# LoRa_Gateway_ESP32_-_DRAFT_3.net
KiCad netlist of a schematic drawn in EAGLE
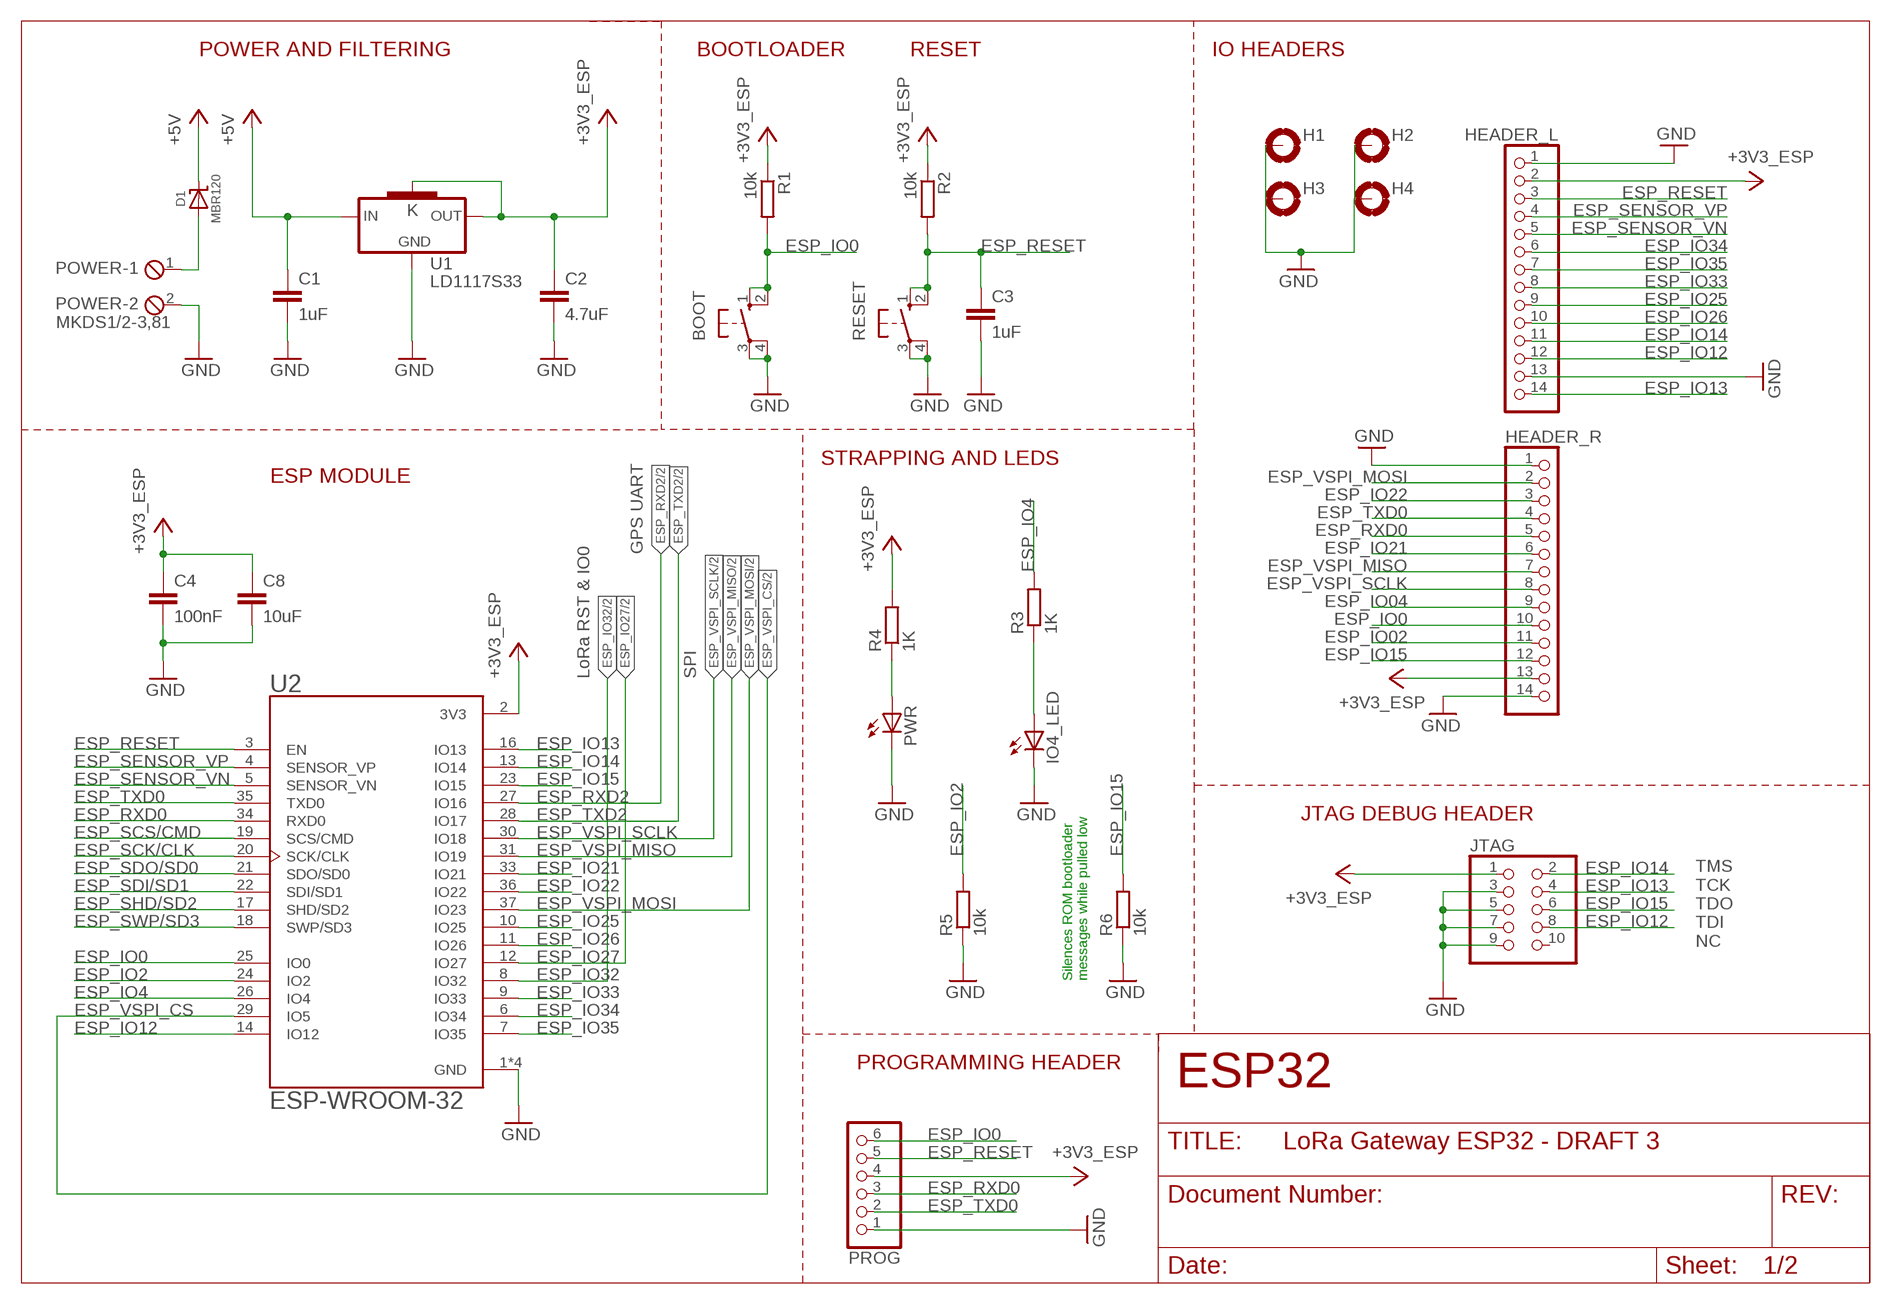
[diagram p0: schematic, sheet 1]
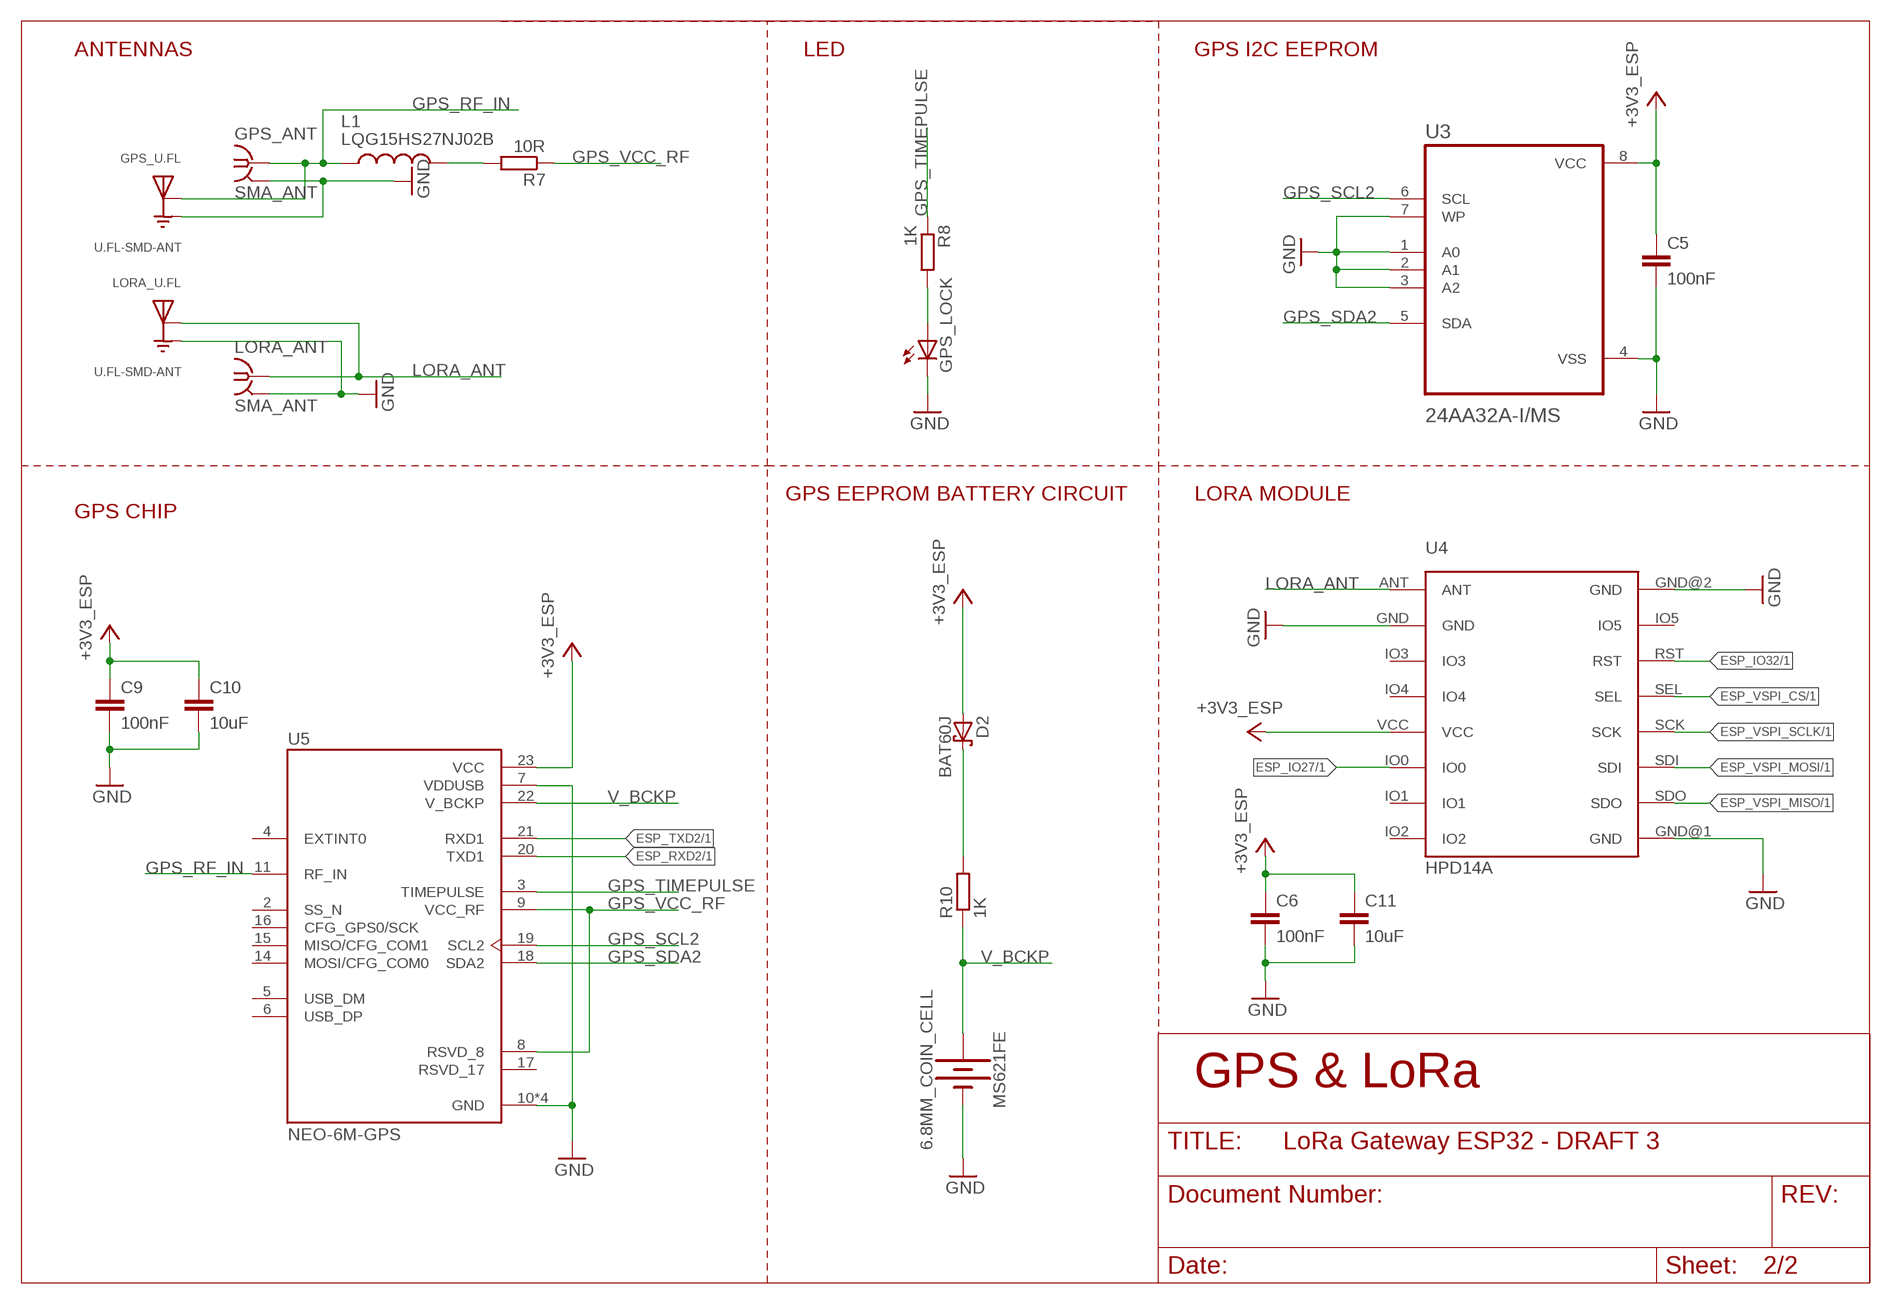
[diagram p1: schematic, sheet 2]

(export (version "E")
  (design (tool "Eeschema 10.0.6"))
  (components
    (comp (ref "C5")
      (value "100nF")
      (footprint "eagle-import:C0805K")
      (libsource (lib "eagle-import") (part "C-EUC0805K"))
    )
    (comp (ref "C6")
      (value "100nF")
      (footprint "eagle-import:C0805K")
      (libsource (lib "eagle-import") (part "C-EUC0805K"))
    )
    (comp (ref "C9")
      (value "100nF")
      (footprint "eagle-import:C0805K")
      (libsource (lib "eagle-import") (part "C-EUC0805K"))
    )
    (comp (ref "C10")
      (value "10uF")
      (footprint "eagle-import:C0805K")
      (libsource (lib "eagle-import") (part "C-EUC0805K"))
    )
    (comp (ref "C11")
      (value "10uF")
      (footprint "eagle-import:C0805K")
      (libsource (lib "eagle-import") (part "C-EUC0805K"))
    )
    (comp (ref "D2")
      (value "BAT60J")
      (footprint "eagle-import:SOD323_ST")
      (libsource (lib "eagle-import") (part "BAT60J"))
    )
    (comp (ref "GPS_ANT")
      (value "SMA_ANT")
      (footprint "eagle-import:BU-SMA-H")
      (libsource (lib "eagle-import") (part "SMA_ANT"))
    )
    (comp (ref "GPS_LOCK")
      (value "LEDCHIP-LED0805")
      (footprint "eagle-import:CHIP-LED0805")
      (libsource (lib "eagle-import") (part "LEDCHIP-LED0805"))
    )
    (comp (ref "GPS_U.FL")
      (value "U.FL-SMD-ANT")
      (footprint "eagle-import:HRS_U.FL-R-SMT-1(10)")
      (fields (field (name "MF") "Hirose") (field (name "MP") "U.FL-R-SMT-1(10)"))
      (libsource (lib "eagle-import") (part "U.FL-SMD-ANT"))
    )
    (comp (ref "L1")
      (value "LQG15HS27NJ02B")
      (footprint "eagle-import:INDC1005X55N")
      (fields (field (name "MF") "Murata"))
      (libsource (lib "eagle-import") (part "LQG15HS27NJ02B"))
    )
    (comp (ref "LORA_ANT")
      (value "SMA_ANT")
      (footprint "eagle-import:BU-SMA-H")
      (libsource (lib "eagle-import") (part "SMA_ANT"))
    )
    (comp (ref "LORA_U.FL")
      (value "U.FL-SMD-ANT")
      (footprint "eagle-import:HRS_U.FL-R-SMT-1(10)")
      (fields (field (name "MF") "Hirose") (field (name "MP") "U.FL-R-SMT-1(10)"))
      (libsource (lib "eagle-import") (part "U.FL-SMD-ANT"))
    )
    (comp (ref "MS621FE")
      (value "6.8MM_COIN_CELL")
      (footprint "eagle-import:BATTCON-6.8MM")
      (libsource (lib "eagle-import") (part "BATTERY-6.8MM_SMD"))
    )
    (comp (ref "R7")
      (value "10R")
      (footprint "eagle-import:R0805")
      (libsource (lib "eagle-import") (part "R-EU_R0805"))
    )
    (comp (ref "R8")
      (value "1K")
      (footprint "eagle-import:R0805")
      (libsource (lib "eagle-import") (part "R-EU_R0805"))
    )
    (comp (ref "R10")
      (value "1K")
      (footprint "eagle-import:R0805")
      (libsource (lib "eagle-import") (part "R-EU_R0805"))
    )
    (comp (ref "U3")
      (value "24AA32A-I/MS")
      (footprint "eagle-import:SOP65P490X110-8N")
      (fields (field (name "MF") "Microchip"))
      (libsource (lib "eagle-import") (part "24AA32A-I/MS"))
    )
    (comp (ref "U4")
      (value "HPD14A")
      (footprint "eagle-import:HPD14A")
      (libsource (lib "eagle-import") (part "HPD14A"))
    )
    (comp (ref "U5")
      (value "NEO-6M-GPS")
      (footprint "eagle-import:XCVR_NEO-6M-GPS")
      (fields (field (name "MF") "u-blox"))
      (libsource (lib "eagle-import") (part "NEO-6M-GPS"))
    )
    (comp (ref "BOOT")
      (value "10-XX")
      (footprint "eagle-import:B3F-10XX")
      (fields (field (name "MPN") "B3F-1000"))
      (libsource (lib "eagle-import") (part "10-XX"))
    )
    (comp (ref "C1")
      (value "1uF")
      (footprint "eagle-import:C0805K")
      (libsource (lib "eagle-import") (part "C-EUC0805K"))
    )
    (comp (ref "C2")
      (value "4.7uF")
      (footprint "eagle-import:C0805K")
      (libsource (lib "eagle-import") (part "C-EUC0805K"))
    )
    (comp (ref "C3")
      (value "1uF")
      (footprint "eagle-import:C0805K")
      (libsource (lib "eagle-import") (part "C-EUC0805K"))
    )
    (comp (ref "C4")
      (value "100nF")
      (footprint "eagle-import:C0805K")
      (libsource (lib "eagle-import") (part "C-EUC0805K"))
    )
    (comp (ref "C8")
      (value "10uF")
      (footprint "eagle-import:C0805K")
      (libsource (lib "eagle-import") (part "C-EUC0805K"))
    )
    (comp (ref "D1")
      (value "MBR120")
      (footprint "eagle-import:SOD-123")
      (libsource (lib "eagle-import") (part "DIODE-SCHOTTKYSOD-123"))
    )
    (comp (ref "H1")
      (value "MOUNT-PAD-ROUND3.2")
      (footprint "eagle-import:3,2-PAD")
      (libsource (lib "eagle-import") (part "MOUNT-PAD-ROUND3.2"))
    )
    (comp (ref "H2")
      (value "MOUNT-PAD-ROUND3.2")
      (footprint "eagle-import:3,2-PAD")
      (libsource (lib "eagle-import") (part "MOUNT-PAD-ROUND3.2"))
    )
    (comp (ref "H3")
      (value "MOUNT-PAD-ROUND3.2")
      (footprint "eagle-import:3,2-PAD")
      (libsource (lib "eagle-import") (part "MOUNT-PAD-ROUND3.2"))
    )
    (comp (ref "H4")
      (value "MOUNT-PAD-ROUND3.2")
      (footprint "eagle-import:3,2-PAD")
      (libsource (lib "eagle-import") (part "MOUNT-PAD-ROUND3.2"))
    )
    (comp (ref "HEADER_L")
      (value "PINHD-1X14")
      (footprint "eagle-import:1X14")
      (libsource (lib "eagle-import") (part "PINHD-1X14"))
    )
    (comp (ref "HEADER_R")
      (value "PINHD-1X14")
      (footprint "eagle-import:1X14")
      (libsource (lib "eagle-import") (part "PINHD-1X14"))
    )
    (comp (ref "IO4_LED")
      (value "LEDCHIP-LED0805")
      (footprint "eagle-import:CHIP-LED0805")
      (libsource (lib "eagle-import") (part "LEDCHIP-LED0805"))
    )
    (comp (ref "JTAG")
      (value "PINHD-2X5")
      (footprint "eagle-import:2X05")
      (libsource (lib "eagle-import") (part "PINHD-2X5"))
    )
    (comp (ref "POWER")
      (value "MKDS1/2-3,81")
      (footprint "eagle-import:2POL381")
      (libsource (lib "eagle-import") (part "MKDS1/2-3,81"))
    )
    (comp (ref "PROG")
      (value "PINHD-1X6")
      (footprint "eagle-import:1X06")
      (libsource (lib "eagle-import") (part "PINHD-1X6"))
    )
    (comp (ref "PWR")
      (value "LEDCHIP-LED0805")
      (footprint "eagle-import:CHIP-LED0805")
      (libsource (lib "eagle-import") (part "LEDCHIP-LED0805"))
    )
    (comp (ref "R1")
      (value "10k")
      (footprint "eagle-import:R0805")
      (libsource (lib "eagle-import") (part "R-EU_R0805"))
    )
    (comp (ref "R2")
      (value "10k")
      (footprint "eagle-import:R0805")
      (libsource (lib "eagle-import") (part "R-EU_R0805"))
    )
    (comp (ref "R3")
      (value "1K")
      (footprint "eagle-import:R0805")
      (libsource (lib "eagle-import") (part "R-EU_R0805"))
    )
    (comp (ref "R4")
      (value "1K")
      (footprint "eagle-import:R0805")
      (libsource (lib "eagle-import") (part "R-EU_R0805"))
    )
    (comp (ref "R5")
      (value "10k")
      (footprint "eagle-import:R0805")
      (libsource (lib "eagle-import") (part "R-EU_R0805"))
    )
    (comp (ref "R6")
      (value "10k")
      (footprint "eagle-import:R0805")
      (libsource (lib "eagle-import") (part "R-EU_R0805"))
    )
    (comp (ref "RESET")
      (value "10-XX")
      (footprint "eagle-import:B3F-10XX")
      (fields (field (name "MPN") "B3F-1000"))
      (libsource (lib "eagle-import") (part "10-XX"))
    )
    (comp (ref "U1")
      (value "LD1117S33")
      (footprint "eagle-import:SOT223")
      (fields (field (name "MF") "STMicroelectronics"))
      (libsource (lib "eagle-import") (part "LD1117S33"))
    )
    (comp (ref "U2")
      (value "ESP-WROOM-32")
      (footprint "eagle-import:MODULE_ESP-WROOM-32")
      (fields (field (name "MF") "Olimex LTD"))
      (libsource (lib "eagle-import") (part "ESP-WROOM-32"))
    )
  )
  (nets
    (net (code "1") (name "+3V3_ESP") (class "Default")
      (node (ref "C10") (pin "1") (pinfunction "1_1") (pintype "passive"))
      (node (ref "C11") (pin "1") (pinfunction "1_1") (pintype "passive"))
      (node (ref "C2") (pin "1") (pinfunction "1_1") (pintype "passive"))
      (node (ref "C4") (pin "1") (pinfunction "1_1") (pintype "passive"))
      (node (ref "C5") (pin "1") (pinfunction "1_1") (pintype "passive"))
      (node (ref "C6") (pin "1") (pinfunction "1_1") (pintype "passive"))
      (node (ref "C8") (pin "1") (pinfunction "1_1") (pintype "passive"))
      (node (ref "C9") (pin "1") (pinfunction "1_1") (pintype "passive"))
      (node (ref "D2") (pin "A") (pinfunction "A_A") (pintype "passive"))
      (node (ref "HEADER_L") (pin "2") (pinfunction "2_2") (pintype "passive"))
      (node (ref "HEADER_R") (pin "13") (pinfunction "13_13") (pintype "passive"))
      (node (ref "JTAG") (pin "1") (pinfunction "1_1") (pintype "passive"))
      (node (ref "PROG") (pin "4") (pinfunction "4_4") (pintype "passive"))
      (node (ref "R1") (pin "1") (pinfunction "1_1") (pintype "passive"))
      (node (ref "R2") (pin "1") (pinfunction "1_1") (pintype "passive"))
      (node (ref "R4") (pin "2") (pinfunction "2_2") (pintype "passive"))
      (node (ref "U1") (pin "2") (pinfunction "OUT_2") (pintype "passive"))
      (node (ref "U1") (pin "4") (pinfunction "K_4") (pintype "passive"))
      (node (ref "U2") (pin "2") (pinfunction "3V3_2") (pintype "power_in"))
      (node (ref "U3") (pin "8") (pinfunction "VCC_8") (pintype "power_in"))
      (node (ref "U4") (pin "VCC") (pinfunction "VCC_VCC") (pintype "bidirectional"))
      (node (ref "U5") (pin "23") (pinfunction "VCC_23") (pintype "power_in"))
    )
    (net (code "2") (name "+5V") (class "Default")
      (node (ref "C1") (pin "1") (pinfunction "1_1") (pintype "passive"))
      (node (ref "D1") (pin "C") (pinfunction "C_C") (pintype "passive"))
      (node (ref "U1") (pin "3") (pinfunction "IN_3") (pintype "input"))
    )
    (net (code "3") (name "ESP_IO0") (class "Default")
      (node (ref "BOOT") (pin "1") (pinfunction "S_1") (pintype "passive"))
      (node (ref "BOOT") (pin "2") (pinfunction "S1_2") (pintype "passive"))
      (node (ref "HEADER_R") (pin "10") (pinfunction "10_10") (pintype "passive"))
      (node (ref "PROG") (pin "6") (pinfunction "6_6") (pintype "passive"))
      (node (ref "R1") (pin "2") (pinfunction "2_2") (pintype "passive"))
      (node (ref "U2") (pin "25") (pinfunction "IO0_25") (pintype "bidirectional"))
    )
    (net (code "4") (name "ESP_IO2") (class "Default")
      (node (ref "R5") (pin "2") (pinfunction "2_2") (pintype "passive"))
      (node (ref "U2") (pin "24") (pinfunction "IO2_24") (pintype "bidirectional"))
    )
    (net (code "5") (name "ESP_IO02") (class "Default")
      (node (ref "HEADER_R") (pin "11") (pinfunction "11_11") (pintype "passive"))
    )
    (net (code "6") (name "ESP_IO4") (class "Default")
      (node (ref "R3") (pin "2") (pinfunction "2_2") (pintype "passive"))
      (node (ref "U2") (pin "26") (pinfunction "IO4_26") (pintype "bidirectional"))
    )
    (net (code "7") (name "ESP_IO04") (class "Default")
      (node (ref "HEADER_R") (pin "9") (pinfunction "9_9") (pintype "passive"))
    )
    (net (code "8") (name "ESP_IO12") (class "Default")
      (node (ref "HEADER_L") (pin "12") (pinfunction "12_12") (pintype "passive"))
      (node (ref "JTAG") (pin "8") (pinfunction "8_8") (pintype "passive"))
      (node (ref "U2") (pin "14") (pinfunction "IO12_14") (pintype "bidirectional"))
    )
    (net (code "9") (name "ESP_IO13") (class "Default")
      (node (ref "HEADER_L") (pin "14") (pinfunction "14_14") (pintype "passive"))
      (node (ref "JTAG") (pin "4") (pinfunction "4_4") (pintype "passive"))
      (node (ref "U2") (pin "16") (pinfunction "IO13_16") (pintype "bidirectional"))
    )
    (net (code "10") (name "ESP_IO14") (class "Default")
      (node (ref "HEADER_L") (pin "11") (pinfunction "11_11") (pintype "passive"))
      (node (ref "JTAG") (pin "2") (pinfunction "2_2") (pintype "passive"))
      (node (ref "U2") (pin "13") (pinfunction "IO14_13") (pintype "bidirectional"))
    )
    (net (code "11") (name "ESP_IO15") (class "Default")
      (node (ref "HEADER_R") (pin "12") (pinfunction "12_12") (pintype "passive"))
      (node (ref "JTAG") (pin "6") (pinfunction "6_6") (pintype "passive"))
      (node (ref "R6") (pin "2") (pinfunction "2_2") (pintype "passive"))
      (node (ref "U2") (pin "23") (pinfunction "IO15_23") (pintype "bidirectional"))
    )
    (net (code "12") (name "ESP_IO21") (class "Default")
      (node (ref "HEADER_R") (pin "6") (pinfunction "6_6") (pintype "passive"))
      (node (ref "U2") (pin "33") (pinfunction "IO21_33") (pintype "bidirectional"))
    )
    (net (code "13") (name "ESP_IO22") (class "Default")
      (node (ref "HEADER_R") (pin "3") (pinfunction "3_3") (pintype "passive"))
      (node (ref "U2") (pin "36") (pinfunction "IO22_36") (pintype "bidirectional"))
    )
    (net (code "14") (name "ESP_IO25") (class "Default")
      (node (ref "HEADER_L") (pin "9") (pinfunction "9_9") (pintype "passive"))
      (node (ref "U2") (pin "10") (pinfunction "IO25_10") (pintype "bidirectional"))
    )
    (net (code "15") (name "ESP_IO26") (class "Default")
      (node (ref "HEADER_L") (pin "10") (pinfunction "10_10") (pintype "passive"))
      (node (ref "U2") (pin "11") (pinfunction "IO26_11") (pintype "bidirectional"))
    )
    (net (code "16") (name "ESP_IO27") (class "Default")
      (node (ref "U2") (pin "12") (pinfunction "IO27_12") (pintype "bidirectional"))
      (node (ref "U4") (pin "IO0") (pinfunction "IO0_IO0") (pintype "bidirectional"))
    )
    (net (code "17") (name "ESP_IO32") (class "Default")
      (node (ref "U2") (pin "8") (pinfunction "IO32_8") (pintype "bidirectional"))
      (node (ref "U4") (pin "RST") (pinfunction "RST_RST") (pintype "bidirectional"))
    )
    (net (code "18") (name "ESP_IO33") (class "Default")
      (node (ref "HEADER_L") (pin "8") (pinfunction "8_8") (pintype "passive"))
      (node (ref "U2") (pin "9") (pinfunction "IO33_9") (pintype "bidirectional"))
    )
    (net (code "19") (name "ESP_IO34") (class "Default")
      (node (ref "HEADER_L") (pin "6") (pinfunction "6_6") (pintype "passive"))
      (node (ref "U2") (pin "6") (pinfunction "IO34_6") (pintype "bidirectional"))
    )
    (net (code "20") (name "ESP_IO35") (class "Default")
      (node (ref "HEADER_L") (pin "7") (pinfunction "7_7") (pintype "passive"))
      (node (ref "U2") (pin "7") (pinfunction "IO35_7") (pintype "bidirectional"))
    )
    (net (code "21") (name "ESP_RESET") (class "Default")
      (node (ref "C3") (pin "1") (pinfunction "1_1") (pintype "passive"))
      (node (ref "HEADER_L") (pin "3") (pinfunction "3_3") (pintype "passive"))
      (node (ref "PROG") (pin "5") (pinfunction "5_5") (pintype "passive"))
      (node (ref "R2") (pin "2") (pinfunction "2_2") (pintype "passive"))
      (node (ref "RESET") (pin "1") (pinfunction "S_1") (pintype "passive"))
      (node (ref "RESET") (pin "2") (pinfunction "S1_2") (pintype "passive"))
      (node (ref "U2") (pin "3") (pinfunction "EN_3") (pintype "input"))
    )
    (net (code "22") (name "ESP_RXD0") (class "Default")
      (node (ref "HEADER_R") (pin "5") (pinfunction "5_5") (pintype "passive"))
      (node (ref "PROG") (pin "3") (pinfunction "3_3") (pintype "passive"))
      (node (ref "U2") (pin "34") (pinfunction "RXD0_34") (pintype "bidirectional"))
    )
    (net (code "23") (name "ESP_RXD2") (class "Default")
      (node (ref "U2") (pin "27") (pinfunction "IO16_27") (pintype "bidirectional"))
      (node (ref "U5") (pin "20") (pinfunction "TXD1_20") (pintype "output"))
    )
    (net (code "24") (name "ESP_SCK{slash}CLK") (class "Default")
      (node (ref "U2") (pin "20") (pinfunction "SCK/CLK_20") (pintype "bidirectional"))
    )
    (net (code "25") (name "ESP_SCS{slash}CMD") (class "Default")
      (node (ref "U2") (pin "19") (pinfunction "SCS/CMD_19") (pintype "bidirectional"))
    )
    (net (code "26") (name "ESP_SDI{slash}SD1") (class "Default")
      (node (ref "U2") (pin "22") (pinfunction "SDI/SD1_22") (pintype "bidirectional"))
    )
    (net (code "27") (name "ESP_SDO{slash}SD0") (class "Default")
      (node (ref "U2") (pin "21") (pinfunction "SDO/SD0_21") (pintype "bidirectional"))
    )
    (net (code "28") (name "ESP_SENSOR_VN") (class "Default")
      (node (ref "HEADER_L") (pin "5") (pinfunction "5_5") (pintype "passive"))
      (node (ref "U2") (pin "5") (pinfunction "SENSOR_VN_5") (pintype "input"))
    )
    (net (code "29") (name "ESP_SENSOR_VP") (class "Default")
      (node (ref "HEADER_L") (pin "4") (pinfunction "4_4") (pintype "passive"))
      (node (ref "U2") (pin "4") (pinfunction "SENSOR_VP_4") (pintype "input"))
    )
    (net (code "30") (name "ESP_SHD{slash}SD2") (class "Default")
      (node (ref "U2") (pin "17") (pinfunction "SHD/SD2_17") (pintype "bidirectional"))
    )
    (net (code "31") (name "ESP_SWP{slash}SD3") (class "Default")
      (node (ref "U2") (pin "18") (pinfunction "SWP/SD3_18") (pintype "bidirectional"))
    )
    (net (code "32") (name "ESP_TXD0") (class "Default")
      (node (ref "HEADER_R") (pin "4") (pinfunction "4_4") (pintype "passive"))
      (node (ref "PROG") (pin "2") (pinfunction "2_2") (pintype "passive"))
      (node (ref "U2") (pin "35") (pinfunction "TXD0_35") (pintype "bidirectional"))
    )
    (net (code "33") (name "ESP_TXD2") (class "Default")
      (node (ref "U2") (pin "28") (pinfunction "IO17_28") (pintype "bidirectional"))
      (node (ref "U5") (pin "21") (pinfunction "RXD1_21") (pintype "input"))
    )
    (net (code "34") (name "ESP_VSPI_CS") (class "Default")
      (node (ref "U2") (pin "29") (pinfunction "IO5_29") (pintype "bidirectional"))
      (node (ref "U4") (pin "SEL") (pinfunction "SEL_SEL") (pintype "bidirectional"))
    )
    (net (code "35") (name "ESP_VSPI_MISO") (class "Default")
      (node (ref "HEADER_R") (pin "7") (pinfunction "7_7") (pintype "passive"))
      (node (ref "U2") (pin "31") (pinfunction "IO19_31") (pintype "bidirectional"))
      (node (ref "U4") (pin "SDO") (pinfunction "SDO_SDO") (pintype "bidirectional"))
    )
    (net (code "36") (name "ESP_VSPI_MOSI") (class "Default")
      (node (ref "HEADER_R") (pin "2") (pinfunction "2_2") (pintype "passive"))
      (node (ref "U2") (pin "37") (pinfunction "IO23_37") (pintype "bidirectional"))
      (node (ref "U4") (pin "SDI") (pinfunction "SDI_SDI") (pintype "bidirectional"))
    )
    (net (code "37") (name "ESP_VSPI_SCLK") (class "Default")
      (node (ref "HEADER_R") (pin "8") (pinfunction "8_8") (pintype "passive"))
      (node (ref "U2") (pin "30") (pinfunction "IO18_30") (pintype "bidirectional"))
      (node (ref "U4") (pin "SCK") (pinfunction "SCK_SCK") (pintype "bidirectional"))
    )
    (net (code "38") (name "GND") (class "Default")
      (node (ref "BOOT") (pin "3") (pinfunction "P_3") (pintype "passive"))
      (node (ref "BOOT") (pin "4") (pinfunction "P1_4") (pintype "passive"))
      (node (ref "C1") (pin "2") (pinfunction "2_2") (pintype "passive"))
      (node (ref "C10") (pin "2") (pinfunction "2_2") (pintype "passive"))
      (node (ref "C11") (pin "2") (pinfunction "2_2") (pintype "passive"))
      (node (ref "C2") (pin "2") (pinfunction "2_2") (pintype "passive"))
      (node (ref "C3") (pin "2") (pinfunction "2_2") (pintype "passive"))
      (node (ref "C4") (pin "2") (pinfunction "2_2") (pintype "passive"))
      (node (ref "C5") (pin "2") (pinfunction "2_2") (pintype "passive"))
      (node (ref "C6") (pin "2") (pinfunction "2_2") (pintype "passive"))
      (node (ref "C8") (pin "2") (pinfunction "2_2") (pintype "passive"))
      (node (ref "C9") (pin "2") (pinfunction "2_2") (pintype "passive"))
      (node (ref "GPS_ANT") (pin "2") (pinfunction "2_2") (pintype "passive"))
      (node (ref "GPS_ANT") (pin "3") (pinfunction "2_3") (pintype "passive"))
      (node (ref "GPS_ANT") (pin "4") (pinfunction "2_4") (pintype "passive"))
      (node (ref "GPS_ANT") (pin "5") (pinfunction "2_5") (pintype "passive"))
      (node (ref "GPS_LOCK") (pin "C") (pinfunction "C_C") (pintype "passive"))
      (node (ref "GPS_U.FL") (pin "1") (pinfunction "GND_1") (pintype "passive"))
      (node (ref "GPS_U.FL") (pin "3") (pinfunction "GND_3") (pintype "passive"))
      (node (ref "H1") (pin "B3,2") (pinfunction "MOUNT_B3,2") (pintype "passive"))
      (node (ref "H2") (pin "B3,2") (pinfunction "MOUNT_B3,2") (pintype "passive"))
      (node (ref "H3") (pin "B3,2") (pinfunction "MOUNT_B3,2") (pintype "passive"))
      (node (ref "H4") (pin "B3,2") (pinfunction "MOUNT_B3,2") (pintype "passive"))
      (node (ref "HEADER_L") (pin "1") (pinfunction "1_1") (pintype "passive"))
      (node (ref "HEADER_L") (pin "13") (pinfunction "13_13") (pintype "passive"))
      (node (ref "HEADER_R") (pin "1") (pinfunction "1_1") (pintype "passive"))
      (node (ref "HEADER_R") (pin "14") (pinfunction "14_14") (pintype "passive"))
      (node (ref "IO4_LED") (pin "C") (pinfunction "C_C") (pintype "passive"))
      (node (ref "JTAG") (pin "3") (pinfunction "3_3") (pintype "passive"))
      (node (ref "JTAG") (pin "5") (pinfunction "5_5") (pintype "passive"))
      (node (ref "JTAG") (pin "7") (pinfunction "7_7") (pintype "passive"))
      (node (ref "JTAG") (pin "9") (pinfunction "9_9") (pintype "passive"))
      (node (ref "LORA_ANT") (pin "2") (pinfunction "2_2") (pintype "passive"))
      (node (ref "LORA_ANT") (pin "3") (pinfunction "2_3") (pintype "passive"))
      (node (ref "LORA_ANT") (pin "4") (pinfunction "2_4") (pintype "passive"))
      (node (ref "LORA_ANT") (pin "5") (pinfunction "2_5") (pintype "passive"))
      (node (ref "LORA_U.FL") (pin "1") (pinfunction "GND_1") (pintype "passive"))
      (node (ref "LORA_U.FL") (pin "3") (pinfunction "GND_3") (pintype "passive"))
      (node (ref "MS621FE") (pin "-") (pinfunction "-_-") (pintype "power_in"))
      (node (ref "POWER") (pin "2") (pinfunction "1_2") (pintype "passive"))
      (node (ref "PROG") (pin "1") (pinfunction "1_1") (pintype "passive"))
      (node (ref "PWR") (pin "C") (pinfunction "C_C") (pintype "passive"))
      (node (ref "R5") (pin "1") (pinfunction "1_1") (pintype "passive"))
      (node (ref "R6") (pin "1") (pinfunction "1_1") (pintype "passive"))
      (node (ref "RESET") (pin "3") (pinfunction "P_3") (pintype "passive"))
      (node (ref "RESET") (pin "4") (pinfunction "P1_4") (pintype "passive"))
      (node (ref "U1") (pin "1") (pinfunction "GND_1") (pintype "input"))
      (node (ref "U2") (pin "1") (pinfunction "GND_1") (pintype "power_in"))
      (node (ref "U2") (pin "1.1") (pinfunction "GND_1.1") (pintype "power_in"))
      (node (ref "U2") (pin "15") (pinfunction "GND_15") (pintype "power_in"))
      (node (ref "U2") (pin "38") (pinfunction "GND_38") (pintype "power_in"))
      (node (ref "U3") (pin "1") (pinfunction "A0_1") (pintype "bidirectional"))
      (node (ref "U3") (pin "2") (pinfunction "A1_2") (pintype "bidirectional"))
      (node (ref "U3") (pin "3") (pinfunction "A2_3") (pintype "bidirectional"))
      (node (ref "U3") (pin "4") (pinfunction "VSS_4") (pintype "power_in"))
      (node (ref "U3") (pin "7") (pinfunction "WP_7") (pintype "input"))
      (node (ref "U4") (pin "GND") (pinfunction "GND_GND") (pintype "bidirectional"))
      (node (ref "U4") (pin "GND@1") (pinfunction "GND_GND@1") (pintype "bidirectional"))
      (node (ref "U4") (pin "GND@2") (pinfunction "GND_GND@2") (pintype "bidirectional"))
      (node (ref "U5") (pin "10") (pinfunction "GND_10") (pintype "power_in"))
      (node (ref "U5") (pin "12") (pinfunction "GND_12") (pintype "power_in"))
      (node (ref "U5") (pin "13") (pinfunction "GND_13") (pintype "power_in"))
      (node (ref "U5") (pin "24") (pinfunction "GND_24") (pintype "power_in"))
      (node (ref "U5") (pin "7") (pinfunction "VDDUSB_7") (pintype "power_in"))
    )
    (net (code "39") (name "GPS_RF_IN") (class "Default")
      (node (ref "GPS_ANT") (pin "1") (pinfunction "1_1") (pintype "passive"))
      (node (ref "GPS_U.FL") (pin "2") (pinfunction "SIG_2") (pintype "passive"))
      (node (ref "L1") (pin "1") (pinfunction "1_1") (pintype "passive"))
      (node (ref "U5") (pin "11") (pinfunction "RF_IN_11") (pintype "input"))
    )
    (net (code "40") (name "GPS_SCL2") (class "Default")
      (node (ref "U3") (pin "6") (pinfunction "SCL_6") (pintype "input"))
      (node (ref "U5") (pin "19") (pinfunction "SCL2_19") (pintype "bidirectional"))
    )
    (net (code "41") (name "GPS_SDA2") (class "Default")
      (node (ref "U3") (pin "5") (pinfunction "SDA_5") (pintype "bidirectional"))
      (node (ref "U5") (pin "18") (pinfunction "SDA2_18") (pintype "bidirectional"))
    )
    (net (code "42") (name "GPS_TIMEPULSE") (class "Default")
      (node (ref "R8") (pin "1") (pinfunction "1_1") (pintype "passive"))
      (node (ref "U5") (pin "3") (pinfunction "TIMEPULSE_3") (pintype "output"))
    )
    (net (code "43") (name "GPS_VCC_RF") (class "Default")
      (node (ref "R7") (pin "1") (pinfunction "1_1") (pintype "passive"))
      (node (ref "U5") (pin "8") (pinfunction "RSVD_8_8") (pintype "passive"))
      (node (ref "U5") (pin "9") (pinfunction "VCC_RF_9") (pintype "output"))
    )
    (net (code "44") (name "LORA_ANT") (class "Default")
      (node (ref "LORA_ANT") (pin "1") (pinfunction "1_1") (pintype "passive"))
      (node (ref "LORA_U.FL") (pin "2") (pinfunction "SIG_2") (pintype "passive"))
      (node (ref "U4") (pin "ANT") (pinfunction "ANT_ANT") (pintype "bidirectional"))
    )
    (net (code "45") (name "Net-(D1-PadA)") (class "Default")
      (node (ref "D1") (pin "A") (pinfunction "A_A") (pintype "passive"))
      (node (ref "POWER") (pin "1") (pinfunction "1_1") (pintype "passive"))
    )
    (net (code "46") (name "Net-(D2-PadC)") (class "Default")
      (node (ref "D2") (pin "C") (pinfunction "C_C") (pintype "passive"))
      (node (ref "R10") (pin "2") (pinfunction "2_2") (pintype "passive"))
    )
    (net (code "47") (name "Net-(GPS_LOCK-PadA)") (class "Default")
      (node (ref "GPS_LOCK") (pin "A") (pinfunction "A_A") (pintype "passive"))
      (node (ref "R8") (pin "2") (pinfunction "2_2") (pintype "passive"))
    )
    (net (code "48") (name "Net-(IO4_LED-PadA)") (class "Default")
      (node (ref "IO4_LED") (pin "A") (pinfunction "A_A") (pintype "passive"))
      (node (ref "R3") (pin "1") (pinfunction "1_1") (pintype "passive"))
    )
    (net (code "49") (name "Net-(L1-Pad2)") (class "Default")
      (node (ref "L1") (pin "2") (pinfunction "2_2") (pintype "passive"))
      (node (ref "R7") (pin "2") (pinfunction "2_2") (pintype "passive"))
    )
    (net (code "50") (name "Net-(PWR-PadA)") (class "Default")
      (node (ref "PWR") (pin "A") (pinfunction "A_A") (pintype "passive"))
      (node (ref "R4") (pin "1") (pinfunction "1_1") (pintype "passive"))
    )
    (net (code "51") (name "V_BCKP") (class "Default")
      (node (ref "MS621FE") (pin "+") (pinfunction "+_+") (pintype "power_in"))
      (node (ref "R10") (pin "1") (pinfunction "1_1") (pintype "passive"))
      (node (ref "U5") (pin "22") (pinfunction "V_BCKP_22") (pintype "power_in"))
    )
    (net (code "52") (name "unconnected-(JTAG-Pad10)") (class "Default")
      (node (ref "JTAG") (pin "10") (pinfunction "10_10") (pintype "passive"))
    )
    (net (code "53") (name "unconnected-(U4-PadIO1)") (class "Default")
      (node (ref "U4") (pin "IO1") (pinfunction "IO1_IO1") (pintype "bidirectional"))
    )
    (net (code "54") (name "unconnected-(U4-PadIO2)") (class "Default")
      (node (ref "U4") (pin "IO2") (pinfunction "IO2_IO2") (pintype "bidirectional"))
    )
    (net (code "55") (name "unconnected-(U4-PadIO3)") (class "Default")
      (node (ref "U4") (pin "IO3") (pinfunction "IO3_IO3") (pintype "bidirectional"))
    )
    (net (code "56") (name "unconnected-(U4-PadIO4)") (class "Default")
      (node (ref "U4") (pin "IO4") (pinfunction "IO4_IO4") (pintype "bidirectional"))
    )
    (net (code "57") (name "unconnected-(U4-PadIO5)") (class "Default")
      (node (ref "U4") (pin "IO5") (pinfunction "IO5_IO5") (pintype "bidirectional"))
    )
    (net (code "58") (name "unconnected-(U5-CFG_GPS0{slash}SCK-Pad16)") (class "Default")
      (node (ref "U5") (pin "16") (pinfunction "CFG_GPS0/SCK_16") (pintype "input"))
    )
    (net (code "59") (name "unconnected-(U5-EXTINT0-Pad4)") (class "Default")
      (node (ref "U5") (pin "4") (pinfunction "EXTINT0_4") (pintype "input"))
    )
    (net (code "60") (name "unconnected-(U5-MISO{slash}CFG_COM1-Pad15)") (class "Default")
      (node (ref "U5") (pin "15") (pinfunction "MISO/CFG_COM1_15") (pintype "input"))
    )
    (net (code "61") (name "unconnected-(U5-MOSI{slash}CFG_COM0-Pad14)") (class "Default")
      (node (ref "U5") (pin "14") (pinfunction "MOSI/CFG_COM0_14") (pintype "bidirectional"))
    )
    (net (code "62") (name "unconnected-(U5-RSVD_17-Pad17)") (class "Default")
      (node (ref "U5") (pin "17") (pinfunction "RSVD_17_17") (pintype "passive"))
    )
    (net (code "63") (name "unconnected-(U5-SS_N-Pad2)") (class "Default")
      (node (ref "U5") (pin "2") (pinfunction "SS_N_2") (pintype "input"))
    )
    (net (code "64") (name "unconnected-(U5-USB_DM-Pad5)") (class "Default")
      (node (ref "U5") (pin "5") (pinfunction "USB_DM_5") (pintype "bidirectional"))
    )
    (net (code "65") (name "unconnected-(U5-USB_DP-Pad6)") (class "Default")
      (node (ref "U5") (pin "6") (pinfunction "USB_DP_6") (pintype "bidirectional"))
    )
  )
)
